# Power.net
KiCad netlist of a schematic drawn in Altium Designer
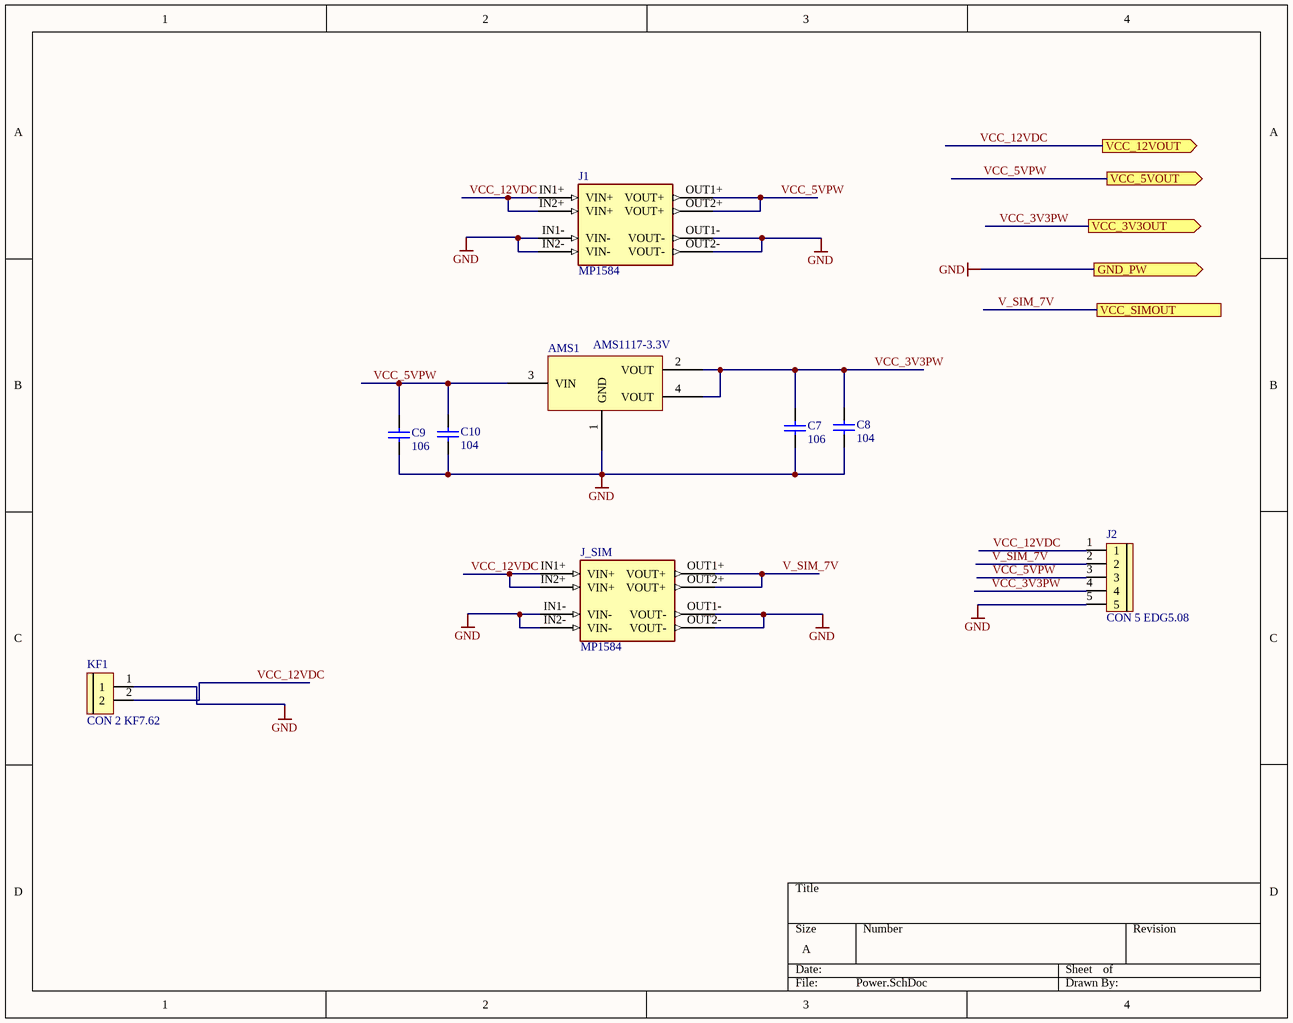
[diagram p0: Power.SchDoc]

(export (version "E")
  (design (tool "Eeschema 10.0.6"))
  (components
    (comp (ref "AMS1")
      (value "AMS1117-3.3V")
      (footprint "SOT223")
      (description "Dán")
      (libsource (lib "Altium_Lib_by_KhueNguyenCreator") (part "AMS1117 SMD"))
    )
    (comp (ref "C7")
      (value "106")
      (footprint "tu 0805")
      (description "Dán")
      (libsource (lib "Altium_Lib_by_KhueNguyenCreator") (part "Tu 0805 106 16V 10%"))
    )
    (comp (ref "C8")
      (value "104")
      (footprint "tu 0805")
      (description "Dán")
      (libsource (lib "Altium_Lib_by_KhueNguyenCreator") (part "Tu 0805 104 50V 10%"))
    )
    (comp (ref "C9")
      (value "106")
      (footprint "tu 0805")
      (description "Dán")
      (libsource (lib "Altium_Lib_by_KhueNguyenCreator") (part "Tu 0805 106 16V 10%"))
    )
    (comp (ref "C10")
      (value "104")
      (footprint "tu 0805")
      (description "Dán")
      (libsource (lib "Altium_Lib_by_KhueNguyenCreator") (part "Tu 0805 104 50V 10%"))
    )
    (comp (ref "J1")
      (value "MP1584")
      (footprint "DC-BRICK")
      (fields (field (name "MF") "Monolithic Power"))
      (libsource (lib "MP1584") (part "MP1584"))
    )
    (comp (ref "J2")
      (value "CON 5 EDG5.08")
      (footprint "CON 5 5EDG5.08")
      (description "Cắm")
      (libsource (lib "Altium_Lib_by_KhueNguyenCreator") (part "CON 5 EDG5.08"))
    )
    (comp (ref "J_SIM")
      (value "MP1584")
      (footprint "DC-BRICK")
      (fields (field (name "MF") "Monolithic Power"))
      (libsource (lib "MP1584") (part "MP1584"))
    )
    (comp (ref "KF1")
      (value "CON 2 KF7.62")
      (footprint "CON 2 KF7.62")
      (description "Cắm")
      (libsource (lib "Altium_Lib_by_KhueNguyenCreator") (part "CON 2 KF7.62"))
    )
  )
  (nets
    (net (code "1") (name "/VCC_3V3PW") (class "Default")
      (node (ref "AMS1") (pin "2") (pinfunction "VOUT_2") (pintype "passive"))
      (node (ref "AMS1") (pin "4") (pinfunction "VOUT_4") (pintype "passive"))
      (node (ref "C7") (pin "1") (pinfunction "1_1") (pintype "passive"))
      (node (ref "C8") (pin "1") (pinfunction "1_1") (pintype "passive"))
      (node (ref "J2") (pin "4") (pinfunction "4_4") (pintype "passive"))
    )
    (net (code "2") (name "/VCC_5VPW") (class "Default")
      (node (ref "AMS1") (pin "3") (pinfunction "VIN_3") (pintype "passive"))
      (node (ref "C10") (pin "1") (pinfunction "1_1") (pintype "passive"))
      (node (ref "C9") (pin "1") (pinfunction "1_1") (pintype "passive"))
      (node (ref "J1") (pin "OUT1+") (pinfunction "VOUT+_OUT1+") (pintype "output"))
      (node (ref "J1") (pin "OUT2+") (pinfunction "VOUT+_OUT2+") (pintype "output"))
      (node (ref "J2") (pin "3") (pinfunction "3_3") (pintype "passive"))
    )
    (net (code "3") (name "/VCC_12VDC") (class "Default")
      (node (ref "J1") (pin "IN1+") (pinfunction "VIN+_IN1+") (pintype "input"))
      (node (ref "J1") (pin "IN2+") (pinfunction "VIN+_IN2+") (pintype "input"))
      (node (ref "J2") (pin "1") (pinfunction "1_1") (pintype "passive"))
      (node (ref "J_SIM") (pin "IN1+") (pinfunction "VIN+_IN1+") (pintype "input"))
      (node (ref "J_SIM") (pin "IN2+") (pinfunction "VIN+_IN2+") (pintype "input"))
      (node (ref "KF1") (pin "2") (pinfunction "2_2") (pintype "passive"))
    )
    (net (code "4") (name "/V_SIM_7V") (class "Default")
      (node (ref "J2") (pin "2") (pinfunction "2_2") (pintype "passive"))
      (node (ref "J_SIM") (pin "OUT1+") (pinfunction "VOUT+_OUT1+") (pintype "output"))
      (node (ref "J_SIM") (pin "OUT2+") (pinfunction "VOUT+_OUT2+") (pintype "output"))
    )
    (net (code "5") (name "GND") (class "Default")
      (node (ref "AMS1") (pin "1") (pinfunction "GND_1") (pintype "passive"))
      (node (ref "C10") (pin "2") (pinfunction "2_2") (pintype "passive"))
      (node (ref "C7") (pin "2") (pinfunction "2_2") (pintype "passive"))
      (node (ref "C8") (pin "2") (pinfunction "2_2") (pintype "passive"))
      (node (ref "C9") (pin "2") (pinfunction "2_2") (pintype "passive"))
      (node (ref "J1") (pin "IN1-") (pinfunction "VIN-_IN1-") (pintype "input"))
      (node (ref "J1") (pin "IN2-") (pinfunction "VIN-_IN2-") (pintype "input"))
      (node (ref "J1") (pin "OUT1-") (pinfunction "VOUT-_OUT1-") (pintype "output"))
      (node (ref "J1") (pin "OUT2-") (pinfunction "VOUT-_OUT2-") (pintype "output"))
      (node (ref "J2") (pin "5") (pinfunction "5_5") (pintype "passive"))
      (node (ref "J_SIM") (pin "IN1-") (pinfunction "VIN-_IN1-") (pintype "input"))
      (node (ref "J_SIM") (pin "IN2-") (pinfunction "VIN-_IN2-") (pintype "input"))
      (node (ref "J_SIM") (pin "OUT1-") (pinfunction "VOUT-_OUT1-") (pintype "output"))
      (node (ref "J_SIM") (pin "OUT2-") (pinfunction "VOUT-_OUT2-") (pintype "output"))
      (node (ref "KF1") (pin "1") (pinfunction "1_1") (pintype "passive"))
    )
  )
)
